# tennka4.net
KiCad netlist of a schematic drawn in EAGLE
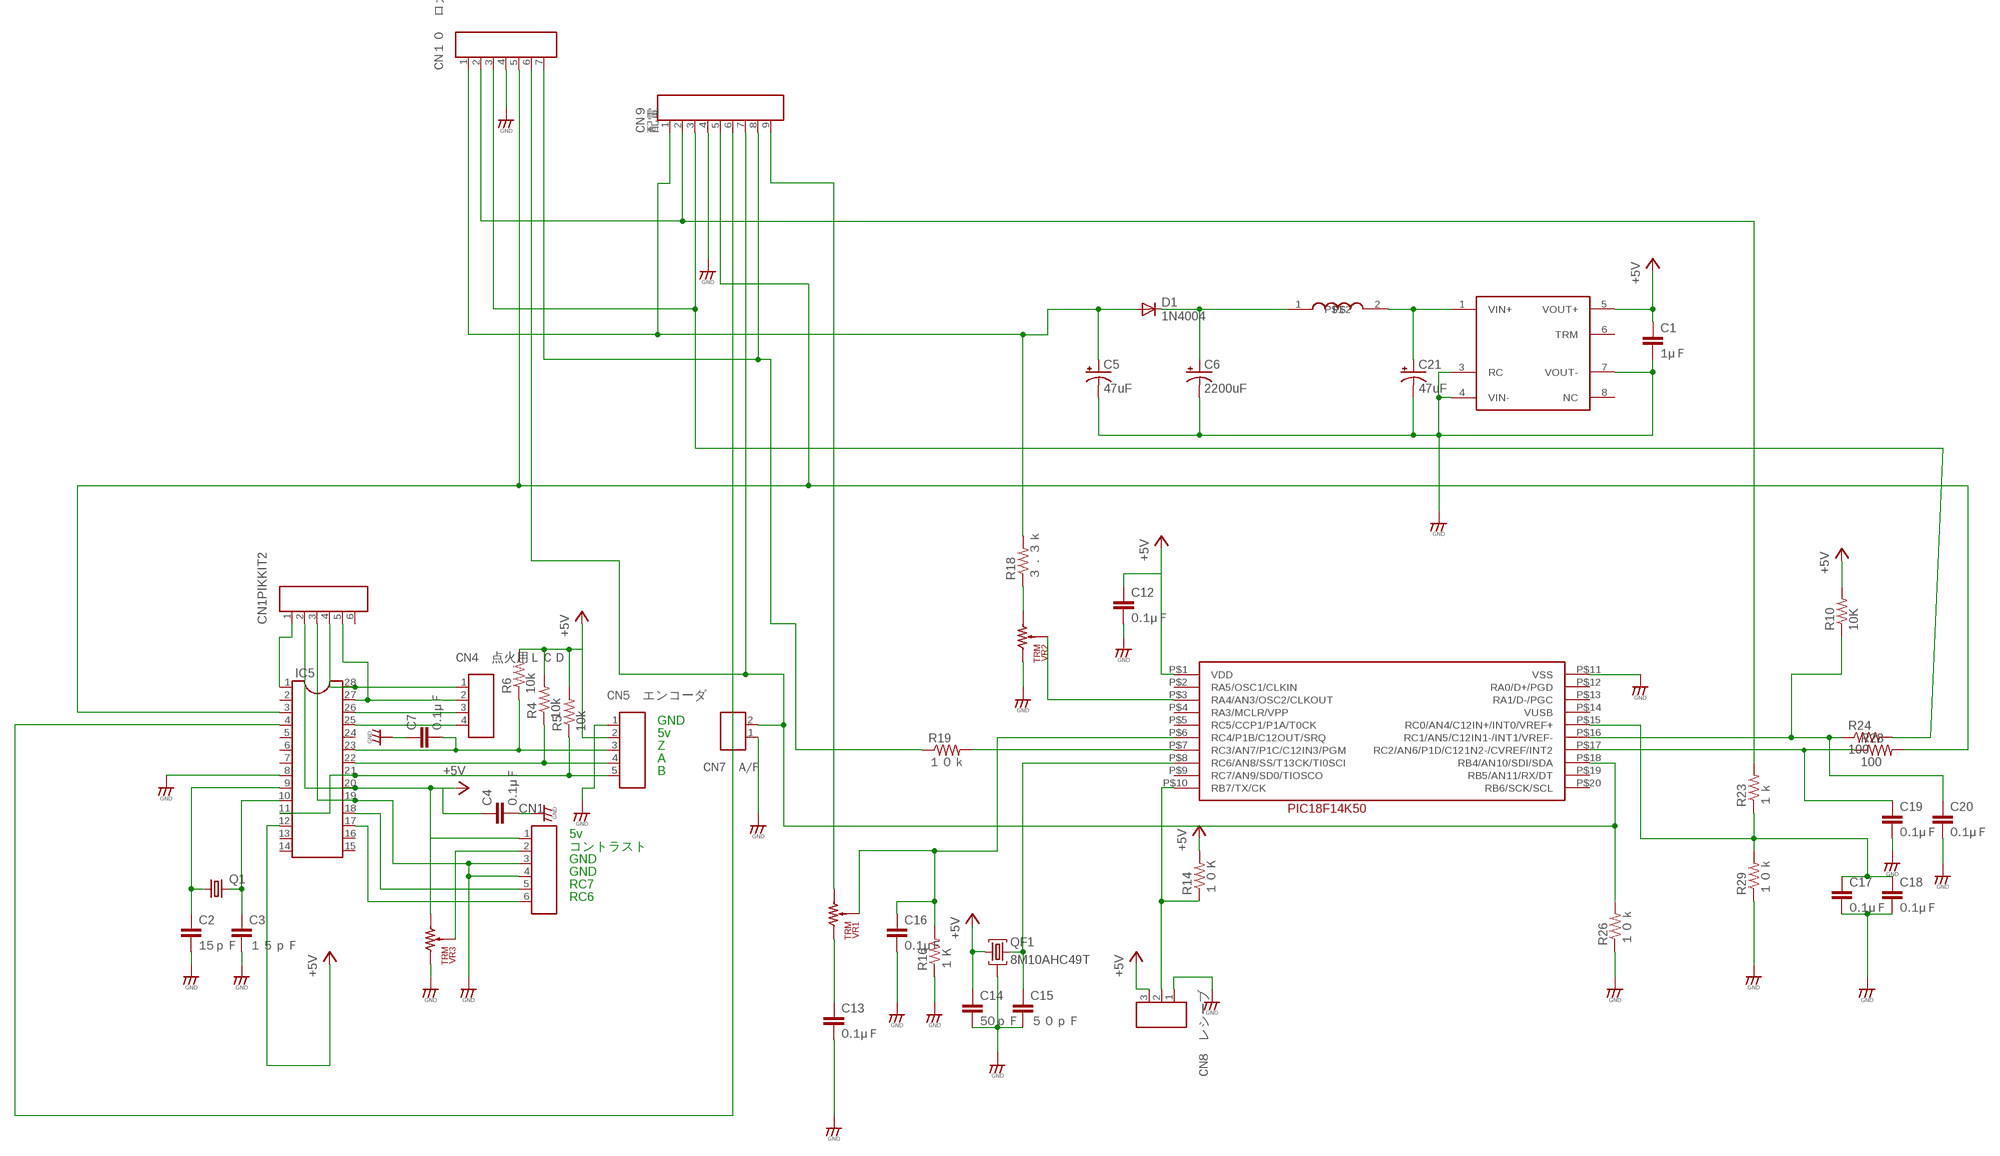
[diagram p0: schematic, sheet 1]

(export (version "E")
  (design (tool "Eeschema 10.0.6"))
  (components
    (comp (ref "C1")
      (value "1μＦ")
      (footprint "eagle-import:C025-024X044")
      (libsource (lib "eagle-import") (part "C-EU025-024X044"))
    )
    (comp (ref "C2")
      (value "15ｐＦ")
      (footprint "eagle-import:C025-024X044")
      (libsource (lib "eagle-import") (part "C-EU025-024X044"))
    )
    (comp (ref "C3")
      (value "１５ｐＦ")
      (footprint "eagle-import:C025-024X044")
      (libsource (lib "eagle-import") (part "C-EU025-024X044"))
    )
    (comp (ref "C4")
      (value "0.1μＦ")
      (footprint "eagle-import:C025-024X044")
      (libsource (lib "eagle-import") (part "C-EU025-024X044"))
    )
    (comp (ref "C5")
      (value "47uF")
      (footprint "eagle-import:E2-4")
      (libsource (lib "eagle-import") (part "CPOL-USE2-4"))
    )
    (comp (ref "C6")
      (value "2200uF")
      (footprint "eagle-import:E5-13")
      (libsource (lib "eagle-import") (part "CPOL-USE5-13"))
    )
    (comp (ref "C7")
      (value "0.1μＦ")
      (footprint "eagle-import:C025-024X044")
      (libsource (lib "eagle-import") (part "C-EU025-024X044"))
    )
    (comp (ref "C12")
      (value "0.1μＦ")
      (footprint "eagle-import:C025-024X044")
      (libsource (lib "eagle-import") (part "C-EU025-024X044"))
    )
    (comp (ref "C13")
      (value "0.1μＦ")
      (footprint "eagle-import:C025-024X044")
      (libsource (lib "eagle-import") (part "C-EU025-024X044"))
    )
    (comp (ref "C14")
      (value "50ｐＦ")
      (footprint "eagle-import:C025-024X044")
      (libsource (lib "eagle-import") (part "C-EU025-024X044"))
    )
    (comp (ref "C15")
      (value "５０ｐＦ")
      (footprint "eagle-import:C025-024X044")
      (libsource (lib "eagle-import") (part "C-EU025-024X044"))
    )
    (comp (ref "C16")
      (value "0.1μＦ")
      (footprint "eagle-import:C025-024X044")
      (libsource (lib "eagle-import") (part "C-EU025-024X044"))
    )
    (comp (ref "C17")
      (value "0.1μＦ")
      (footprint "eagle-import:C025-024X044")
      (libsource (lib "eagle-import") (part "C-EU025-024X044"))
    )
    (comp (ref "C18")
      (value "0.1μＦ")
      (footprint "eagle-import:C025-024X044")
      (libsource (lib "eagle-import") (part "C-EU025-024X044"))
    )
    (comp (ref "C19")
      (value "0.1μＦ")
      (footprint "eagle-import:C025-024X044")
      (libsource (lib "eagle-import") (part "C-EU025-024X044"))
    )
    (comp (ref "C20")
      (value "0.1μＦ")
      (footprint "eagle-import:C025-024X044")
      (libsource (lib "eagle-import") (part "C-EU025-024X044"))
    )
    (comp (ref "C21")
      (value "47uF")
      (footprint "eagle-import:E2-4")
      (libsource (lib "eagle-import") (part "CPOL-USE2-4"))
    )
    (comp (ref "CN1")
      (value "CON_6P")
      (footprint "eagle-import:CON_HRS_DIP_6")
      (libsource (lib "eagle-import") (part "CON_6P"))
    )
    (comp (ref "CN1PIKKIT2")
      (value "CON_6P")
      (footprint "eagle-import:CON_HRS_DIP_6")
      (libsource (lib "eagle-import") (part "CON_6P"))
    )
    (comp (ref "CN4　点火用ＬＣＤ")
      (value "CON_4P")
      (footprint "eagle-import:CON_HRS_DIP_4")
      (libsource (lib "eagle-import") (part "CON_4P"))
    )
    (comp (ref "CN5　エンコーダ")
      (value "CON_5P")
      (footprint "eagle-import:CON_HRS_DIP_5")
      (libsource (lib "eagle-import") (part "CON_5P"))
    )
    (comp (ref "CN7　A/F")
      (value "CON_2P")
      (footprint "eagle-import:CON_HRS_DIP_2")
      (libsource (lib "eagle-import") (part "CON_2P"))
    )
    (comp (ref "CN8　レシーブ")
      (value "CON_3P")
      (footprint "eagle-import:CON_HRS_DIP_3")
      (libsource (lib "eagle-import") (part "CON_3P"))
    )
    (comp (ref "CN１０　ロガー")
      (value "CON_7P")
      (footprint "eagle-import:CON_HRS_DIP_7")
      (libsource (lib "eagle-import") (part "CON_7P"))
    )
    (comp (ref "CN９")
      (value "配電")
      (footprint "eagle-import:CON_HRS_DIP_9")
      (libsource (lib "eagle-import") (part "CON_9P"))
    )
    (comp (ref "D1")
      (value "1N4004")
      (footprint "eagle-import:DO41-10")
      (libsource (lib "eagle-import") (part "1N4004"))
    )
    (comp (ref "IC5")
      (value "DIL28-3")
      (footprint "eagle-import:DIL28-3")
      (libsource (lib "eagle-import") (part "DIL28-3"))
    )
    (comp (ref "IC6")
      (value "PIC18F14K50")
      (footprint "eagle-import:PIC18F14K50")
      (libsource (lib "eagle-import") (part "PIC18F14K50"))
    )
    (comp (ref "LHL13NB101K1")
      (value "LHL13NB101K")
      (footprint "eagle-import:LHL13NB101K")
      (libsource (lib "eagle-import") (part "LHL13NB101K"))
    )
    (comp (ref "Q1")
      (value "CRYSTALHC49S")
      (footprint "eagle-import:HC49_S")
      (libsource (lib "eagle-import") (part "CRYSTALHC49S"))
    )
    (comp (ref "QF1")
      (value "8M10AHC49T")
      (footprint "eagle-import:HC49U")
      (libsource (lib "eagle-import") (part "8M10AHC49T"))
    )
    (comp (ref "R4")
      (value "10k")
      (footprint "eagle-import:0207_7")
      (libsource (lib "eagle-import") (part "R-US_0207/7"))
    )
    (comp (ref "R5")
      (value "10k")
      (footprint "eagle-import:0207_7")
      (libsource (lib "eagle-import") (part "R-US_0207/7"))
    )
    (comp (ref "R6")
      (value "10k")
      (footprint "eagle-import:0207_7")
      (libsource (lib "eagle-import") (part "R-US_0207/7"))
    )
    (comp (ref "R10")
      (value "10K")
      (footprint "eagle-import:0207_7")
      (libsource (lib "eagle-import") (part "R-US_0207/7"))
    )
    (comp (ref "R14")
      (value "１０Ｋ")
      (footprint "eagle-import:0207_7")
      (libsource (lib "eagle-import") (part "R-US_0207/7"))
    )
    (comp (ref "R16")
      (value "１Ｋ")
      (footprint "eagle-import:0207_7")
      (libsource (lib "eagle-import") (part "R-US_0207/7"))
    )
    (comp (ref "R18")
      (value "３．３ｋ")
      (footprint "eagle-import:0207_7")
      (libsource (lib "eagle-import") (part "R-US_0207/7"))
    )
    (comp (ref "R19")
      (value "１０ｋ")
      (footprint "eagle-import:0207_7")
      (libsource (lib "eagle-import") (part "R-US_0207/7"))
    )
    (comp (ref "R23")
      (value "１ｋ")
      (footprint "eagle-import:0207_7")
      (libsource (lib "eagle-import") (part "R-US_0207/7"))
    )
    (comp (ref "R24")
      (value "100")
      (footprint "eagle-import:0207_7")
      (libsource (lib "eagle-import") (part "R-US_0207/7"))
    )
    (comp (ref "R26")
      (value "１０ｋ")
      (footprint "eagle-import:0207_7")
      (libsource (lib "eagle-import") (part "R-US_0207/7"))
    )
    (comp (ref "R28")
      (value "100")
      (footprint "eagle-import:0207_7")
      (libsource (lib "eagle-import") (part "R-US_0207/7"))
    )
    (comp (ref "R29")
      (value "１０ｋ")
      (footprint "eagle-import:0207_7")
      (libsource (lib "eagle-import") (part "R-US_0207/7"))
    )
    (comp (ref "U$3")
      (value "DCDC-CC3-1205SF-E")
      (footprint "eagle-import:DCDC-CC3-1205SF-E")
      (libsource (lib "eagle-import") (part "DCDC-CC3-1205SF-E"))
    )
    (comp (ref "VR1")
      (value "TRM")
      (footprint "eagle-import:TRM")
      (libsource (lib "eagle-import") (part "TRM"))
    )
    (comp (ref "VR2")
      (value "TRM")
      (footprint "eagle-import:TRM")
      (libsource (lib "eagle-import") (part "TRM"))
    )
    (comp (ref "VR3")
      (value "TRM")
      (footprint "eagle-import:TRM")
      (libsource (lib "eagle-import") (part "TRM"))
    )
  )
  (nets
    (net (code "1") (name "+5V") (class "Default")
      (node (ref "C1") (pin "1") (pinfunction "1_1") (pintype "passive"))
      (node (ref "C12") (pin "1") (pinfunction "1_1") (pintype "passive"))
      (node (ref "C14") (pin "1") (pinfunction "1_1") (pintype "passive"))
      (node (ref "C4") (pin "1") (pinfunction "1_1") (pintype "passive"))
      (node (ref "CN1") (pin "1") (pinfunction "1_1") (pintype "passive"))
      (node (ref "CN1PIKKIT2") (pin "2") (pinfunction "2_2") (pintype "passive"))
      (node (ref "CN5　エンコーダ") (pin "2") (pinfunction "2_2") (pintype "passive"))
      (node (ref "CN8　レシーブ") (pin "3") (pinfunction "3_3") (pintype "passive"))
      (node (ref "IC5") (pin "12") (pinfunction "12_12") (pintype "passive"))
      (node (ref "IC5") (pin "20") (pinfunction "20_20") (pintype "passive"))
      (node (ref "IC6") (pin "P$1") (pinfunction "VDD_P$1") (pintype "power_in"))
      (node (ref "QF1") (pin "1") (pinfunction "1_1") (pintype "passive"))
      (node (ref "R10") (pin "2") (pinfunction "2_2") (pintype "passive"))
      (node (ref "R14") (pin "2") (pinfunction "2_2") (pintype "passive"))
      (node (ref "R4") (pin "2") (pinfunction "2_2") (pintype "passive"))
      (node (ref "R5") (pin "2") (pinfunction "2_2") (pintype "passive"))
      (node (ref "R6") (pin "2") (pinfunction "2_2") (pintype "passive"))
      (node (ref "U$3") (pin "5") (pinfunction "VOUT+_5") (pintype "bidirectional"))
      (node (ref "VR3") (pin "P$1") (pinfunction "P$1_P$1") (pintype "passive"))
    )
    (net (code "2") (name "/RA3{slash}MCLR{slash}VPP") (class "Default")
      (node (ref "IC6") (pin "P$4") (pinfunction "RA3/MCLR/VPP_P$4") (pintype "power_in"))
    )
    (net (code "3") (name "GND") (class "Default")
      (node (ref "C1") (pin "2") (pinfunction "2_2") (pintype "passive"))
      (node (ref "C12") (pin "2") (pinfunction "2_2") (pintype "passive"))
      (node (ref "C13") (pin "2") (pinfunction "2_2") (pintype "passive"))
      (node (ref "C14") (pin "2") (pinfunction "2_2") (pintype "passive"))
      (node (ref "C15") (pin "2") (pinfunction "2_2") (pintype "passive"))
      (node (ref "C16") (pin "2") (pinfunction "2_2") (pintype "passive"))
      (node (ref "C17") (pin "2") (pinfunction "2_2") (pintype "passive"))
      (node (ref "C18") (pin "2") (pinfunction "2_2") (pintype "passive"))
      (node (ref "C19") (pin "2") (pinfunction "2_2") (pintype "passive"))
      (node (ref "C2") (pin "2") (pinfunction "2_2") (pintype "passive"))
      (node (ref "C20") (pin "2") (pinfunction "2_2") (pintype "passive"))
      (node (ref "C21") (pin "-") (pinfunction "-_-") (pintype "passive"))
      (node (ref "C3") (pin "2") (pinfunction "2_2") (pintype "passive"))
      (node (ref "C4") (pin "2") (pinfunction "2_2") (pintype "passive"))
      (node (ref "C5") (pin "-") (pinfunction "-_-") (pintype "passive"))
      (node (ref "C6") (pin "-") (pinfunction "-_-") (pintype "passive"))
      (node (ref "C7") (pin "1") (pinfunction "1_1") (pintype "passive"))
      (node (ref "CN1") (pin "3") (pinfunction "3_3") (pintype "passive"))
      (node (ref "CN1") (pin "4") (pinfunction "4_4") (pintype "passive"))
      (node (ref "CN1PIKKIT2") (pin "3") (pinfunction "3_3") (pintype "passive"))
      (node (ref "CN5　エンコーダ") (pin "1") (pinfunction "1_1") (pintype "passive"))
      (node (ref "CN7　A/F") (pin "1") (pinfunction "1_1") (pintype "passive"))
      (node (ref "CN8　レシーブ") (pin "1") (pinfunction "1_1") (pintype "passive"))
      (node (ref "CN１０　ロガー") (pin "4") (pinfunction "4_4") (pintype "passive"))
      (node (ref "CN９") (pin "4") (pinfunction "4_4") (pintype "passive"))
      (node (ref "IC5") (pin "19") (pinfunction "19_19") (pintype "passive"))
      (node (ref "IC5") (pin "8") (pinfunction "8_8") (pintype "passive"))
      (node (ref "IC6") (pin "P$11") (pinfunction "VSS_P$11") (pintype "power_in"))
      (node (ref "QF1") (pin "2") (pinfunction "2_2") (pintype "passive"))
      (node (ref "R16") (pin "1") (pinfunction "1_1") (pintype "passive"))
      (node (ref "R26") (pin "1") (pinfunction "1_1") (pintype "passive"))
      (node (ref "R29") (pin "1") (pinfunction "1_1") (pintype "passive"))
      (node (ref "U$3") (pin "3") (pinfunction "RC_3") (pintype "bidirectional"))
      (node (ref "U$3") (pin "4") (pinfunction "VIN-_4") (pintype "bidirectional"))
      (node (ref "U$3") (pin "7") (pinfunction "VOUT-_7") (pintype "bidirectional"))
      (node (ref "VR2") (pin "P$3") (pinfunction "P$3_P$3") (pintype "passive"))
      (node (ref "VR3") (pin "P$3") (pinfunction "P$3_P$3") (pintype "passive"))
    )
    (net (code "4") (name "Net-(C2-Pad1)") (class "Default")
      (node (ref "C2") (pin "1") (pinfunction "1_1") (pintype "passive"))
      (node (ref "IC5") (pin "9") (pinfunction "9_9") (pintype "passive"))
      (node (ref "Q1") (pin "1") (pinfunction "1_1") (pintype "passive"))
    )
    (net (code "5") (name "Net-(C3-Pad1)") (class "Default")
      (node (ref "C3") (pin "1") (pinfunction "1_1") (pintype "passive"))
      (node (ref "IC5") (pin "10") (pinfunction "10_10") (pintype "passive"))
      (node (ref "Q1") (pin "2") (pinfunction "2_2") (pintype "passive"))
    )
    (net (code "6") (name "Net-(C5-Pad+)") (class "Default")
      (node (ref "C5") (pin "+") (pinfunction "+_+") (pintype "passive"))
      (node (ref "CN１０　ロガー") (pin "1") (pinfunction "1_1") (pintype "passive"))
      (node (ref "CN９") (pin "1") (pinfunction "1_1") (pintype "passive"))
      (node (ref "D1") (pin "A") (pinfunction "A_A") (pintype "passive"))
      (node (ref "R18") (pin "2") (pinfunction "2_2") (pintype "passive"))
    )
    (net (code "7") (name "Net-(C7-Pad2)") (class "Default")
      (node (ref "C7") (pin "2") (pinfunction "2_2") (pintype "passive"))
      (node (ref "CN5　エンコーダ") (pin "3") (pinfunction "3_3") (pintype "passive"))
      (node (ref "IC5") (pin "23") (pinfunction "23_23") (pintype "passive"))
      (node (ref "R6") (pin "1") (pinfunction "1_1") (pintype "passive"))
    )
    (net (code "8") (name "Net-(C13-Pad1)") (class "Default")
      (node (ref "C13") (pin "1") (pinfunction "1_1") (pintype "passive"))
      (node (ref "VR1") (pin "P$3") (pinfunction "P$3_P$3") (pintype "passive"))
    )
    (net (code "9") (name "Net-(CN1-Pad2)") (class "Default")
      (node (ref "CN1") (pin "2") (pinfunction "2_2") (pintype "passive"))
      (node (ref "VR3") (pin "P$2") (pinfunction "P$2_P$2") (pintype "passive"))
    )
    (net (code "10") (name "Net-(CN1-Pad5)") (class "Default")
      (node (ref "CN1") (pin "5") (pinfunction "5_5") (pintype "passive"))
      (node (ref "IC5") (pin "18") (pinfunction "18_18") (pintype "passive"))
    )
    (net (code "11") (name "Net-(CN1-Pad6)") (class "Default")
      (node (ref "CN1") (pin "6") (pinfunction "6_6") (pintype "passive"))
      (node (ref "IC5") (pin "17") (pinfunction "17_17") (pintype "passive"))
    )
    (net (code "12") (name "Net-(CN1PIKKIT2-Pad1)") (class "Default")
      (node (ref "CN1PIKKIT2") (pin "1") (pinfunction "1_1") (pintype "passive"))
      (node (ref "IC5") (pin "1") (pinfunction "1_1") (pintype "passive"))
    )
    (net (code "13") (name "Net-(CN1PIKKIT2-Pad4)") (class "Default")
      (node (ref "CN1PIKKIT2") (pin "4") (pinfunction "4_4") (pintype "passive"))
      (node (ref "CN4　点火用ＬＣＤ") (pin "1") (pinfunction "1_1") (pintype "passive"))
      (node (ref "IC5") (pin "28") (pinfunction "28_28") (pintype "passive"))
    )
    (net (code "14") (name "Net-(CN1PIKKIT2-Pad5)") (class "Default")
      (node (ref "CN1PIKKIT2") (pin "5") (pinfunction "5_5") (pintype "passive"))
      (node (ref "CN4　点火用ＬＣＤ") (pin "2") (pinfunction "2_2") (pintype "passive"))
      (node (ref "IC5") (pin "27") (pinfunction "27_27") (pintype "passive"))
    )
    (net (code "15") (name "Net-(CN4　点火用ＬＣＤ-Pad3)") (class "Default")
      (node (ref "CN4　点火用ＬＣＤ") (pin "3") (pinfunction "3_3") (pintype "passive"))
      (node (ref "IC5") (pin "26") (pinfunction "26_26") (pintype "passive"))
    )
    (net (code "16") (name "Net-(CN4　点火用ＬＣＤ-Pad4)") (class "Default")
      (node (ref "CN4　点火用ＬＣＤ") (pin "4") (pinfunction "4_4") (pintype "passive"))
      (node (ref "IC5") (pin "25") (pinfunction "25_25") (pintype "passive"))
    )
    (net (code "17") (name "Net-(CN5　エンコーダ-Pad4)") (class "Default")
      (node (ref "CN5　エンコーダ") (pin "4") (pinfunction "4_4") (pintype "passive"))
      (node (ref "IC5") (pin "22") (pinfunction "22_22") (pintype "passive"))
      (node (ref "R4") (pin "1") (pinfunction "1_1") (pintype "passive"))
    )
    (net (code "18") (name "Net-(CN5　エンコーダ-Pad5)") (class "Default")
      (node (ref "CN5　エンコーダ") (pin "5") (pinfunction "5_5") (pintype "passive"))
      (node (ref "IC5") (pin "11") (pinfunction "11_11") (pintype "passive"))
      (node (ref "IC5") (pin "21") (pinfunction "21_21") (pintype "passive"))
      (node (ref "R5") (pin "1") (pinfunction "1_1") (pintype "passive"))
    )
    (net (code "19") (name "Net-(CN１０　ロガー-Pad2)") (class "Default")
      (node (ref "CN１０　ロガー") (pin "2") (pinfunction "2_2") (pintype "passive"))
      (node (ref "CN９") (pin "2") (pinfunction "2_2") (pintype "passive"))
      (node (ref "R23") (pin "2") (pinfunction "2_2") (pintype "passive"))
    )
    (net (code "20") (name "Net-(CN１０　ロガー-Pad3)") (class "Default")
      (node (ref "CN１０　ロガー") (pin "3") (pinfunction "3_3") (pintype "passive"))
      (node (ref "CN９") (pin "3") (pinfunction "3_3") (pintype "passive"))
      (node (ref "R24") (pin "2") (pinfunction "2_2") (pintype "passive"))
    )
    (net (code "21") (name "Net-(CN１０　ロガー-Pad5)") (class "Default")
      (node (ref "CN１０　ロガー") (pin "5") (pinfunction "5_5") (pintype "passive"))
      (node (ref "CN９") (pin "5") (pinfunction "5_5") (pintype "passive"))
      (node (ref "IC5") (pin "3") (pinfunction "3_3") (pintype "passive"))
      (node (ref "R28") (pin "2") (pinfunction "2_2") (pintype "passive"))
    )
    (net (code "22") (name "Net-(CN１０　ロガー-Pad7)") (class "Default")
      (node (ref "CN１０　ロガー") (pin "7") (pinfunction "7_7") (pintype "passive"))
      (node (ref "CN９") (pin "8") (pinfunction "8_8") (pintype "passive"))
      (node (ref "R19") (pin "1") (pinfunction "1_1") (pintype "passive"))
    )
    (net (code "23") (name "Net-(CN９-Pad6)") (class "Default")
      (node (ref "CN９") (pin "6") (pinfunction "6_6") (pintype "passive"))
      (node (ref "IC5") (pin "4") (pinfunction "4_4") (pintype "passive"))
    )
    (net (code "24") (name "Net-(CN９-Pad9)") (class "Default")
      (node (ref "CN９") (pin "9") (pinfunction "9_9") (pintype "passive"))
      (node (ref "VR1") (pin "P$1") (pinfunction "P$1_P$1") (pintype "passive"))
    )
    (net (code "25") (name "Net-(IC6-RA4{slash}AN3{slash}OSC2{slash}CLKOUT)") (class "Default")
      (node (ref "IC6") (pin "P$3") (pinfunction "RA4/AN3/OSC2/CLKOUT_P$3") (pintype "bidirectional"))
      (node (ref "VR2") (pin "P$2") (pinfunction "P$2_P$2") (pintype "passive"))
    )
    (net (code "26") (name "Net-(IC6-RB4{slash}AN10{slash}SDI{slash}SDA)") (class "Default")
      (node (ref "CN7　A/F") (pin "2") (pinfunction "2_2") (pintype "passive"))
      (node (ref "CN１０　ロガー") (pin "6") (pinfunction "6_6") (pintype "passive"))
      (node (ref "CN９") (pin "7") (pinfunction "7_7") (pintype "passive"))
      (node (ref "IC6") (pin "P$18") (pinfunction "RB4/AN10/SDI/SDA_P$18") (pintype "bidirectional"))
      (node (ref "R26") (pin "2") (pinfunction "2_2") (pintype "passive"))
    )
    (net (code "27") (name "Net-(IC6-RB7{slash}TX{slash}CK)") (class "Default")
      (node (ref "CN8　レシーブ") (pin "2") (pinfunction "2_2") (pintype "passive"))
      (node (ref "IC6") (pin "P$10") (pinfunction "RB7/TX/CK_P$10") (pintype "bidirectional"))
      (node (ref "R14") (pin "1") (pinfunction "1_1") (pintype "passive"))
    )
    (net (code "28") (name "Net-(IC6-RC0{slash}AN4{slash}C12IN+{slash}INT0{slash}VREF+)") (class "Default")
      (node (ref "C17") (pin "1") (pinfunction "1_1") (pintype "passive"))
      (node (ref "C18") (pin "1") (pinfunction "1_1") (pintype "passive"))
      (node (ref "IC6") (pin "P$15") (pinfunction "RC0/AN4/C12IN+/INT0/VREF+_P$15") (pintype "input"))
      (node (ref "R23") (pin "1") (pinfunction "1_1") (pintype "passive"))
      (node (ref "R29") (pin "2") (pinfunction "2_2") (pintype "passive"))
    )
    (net (code "29") (name "Net-(IC6-RC1{slash}AN5{slash}C12IN1-{slash}INT1{slash}VREF-)") (class "Default")
      (node (ref "C20") (pin "1") (pinfunction "1_1") (pintype "passive"))
      (node (ref "IC6") (pin "P$16") (pinfunction "RC1/AN5/C12IN1-/INT1/VREF-_P$16") (pintype "bidirectional"))
      (node (ref "R10") (pin "1") (pinfunction "1_1") (pintype "passive"))
      (node (ref "R24") (pin "1") (pinfunction "1_1") (pintype "passive"))
    )
    (net (code "30") (name "Net-(IC6-RC2{slash}AN6{slash}P1D{slash}C121N2-{slash}CVREF{slash}INT2)") (class "Default")
      (node (ref "C19") (pin "1") (pinfunction "1_1") (pintype "passive"))
      (node (ref "IC6") (pin "P$17") (pinfunction "RC2/AN6/P1D/C121N2-/CVREF/INT2_P$17") (pintype "bidirectional"))
      (node (ref "R28") (pin "1") (pinfunction "1_1") (pintype "passive"))
    )
    (net (code "31") (name "Net-(IC6-RC3{slash}AN7{slash}P1C{slash}C12IN3{slash}PGM)") (class "Default")
      (node (ref "IC6") (pin "P$7") (pinfunction "RC3/AN7/P1C/C12IN3/PGM_P$7") (pintype "bidirectional"))
      (node (ref "R19") (pin "2") (pinfunction "2_2") (pintype "passive"))
    )
    (net (code "32") (name "Net-(IC6-RC4{slash}P1B{slash}C12OUT{slash}SRQ)") (class "Default")
      (node (ref "C16") (pin "1") (pinfunction "1_1") (pintype "passive"))
      (node (ref "IC6") (pin "P$6") (pinfunction "RC4/P1B/C12OUT/SRQ_P$6") (pintype "bidirectional"))
      (node (ref "R16") (pin "2") (pinfunction "2_2") (pintype "passive"))
      (node (ref "VR1") (pin "P$2") (pinfunction "P$2_P$2") (pintype "passive"))
    )
    (net (code "33") (name "Net-(IC6-RC6{slash}AN8{slash}SS{slash}T13CK{slash}TI0SCI)") (class "Default")
      (node (ref "C15") (pin "1") (pinfunction "1_1") (pintype "passive"))
      (node (ref "IC6") (pin "P$8") (pinfunction "RC6/AN8/SS/T13CK/TI0SCI_P$8") (pintype "bidirectional"))
      (node (ref "QF1") (pin "3") (pinfunction "3_3") (pintype "passive"))
    )
    (net (code "34") (name "Net-(LHL13NB101K1-P$1)") (class "Default")
      (node (ref "C6") (pin "+") (pinfunction "+_+") (pintype "passive"))
      (node (ref "D1") (pin "C") (pinfunction "C_C") (pintype "passive"))
      (node (ref "LHL13NB101K1") (pin "1") (pinfunction "P$1_1") (pintype "bidirectional"))
    )
    (net (code "35") (name "Net-(LHL13NB101K1-P$2)") (class "Default")
      (node (ref "C21") (pin "+") (pinfunction "+_+") (pintype "passive"))
      (node (ref "LHL13NB101K1") (pin "2") (pinfunction "P$2_2") (pintype "bidirectional"))
      (node (ref "U$3") (pin "1") (pinfunction "VIN+_1") (pintype "bidirectional"))
    )
    (net (code "36") (name "Net-(R18-Pad1)") (class "Default")
      (node (ref "R18") (pin "1") (pinfunction "1_1") (pintype "passive"))
      (node (ref "VR2") (pin "P$1") (pinfunction "P$1_P$1") (pintype "passive"))
    )
    (net (code "37") (name "unconnected-(CN1PIKKIT2-Pad6)") (class "Default")
      (node (ref "CN1PIKKIT2") (pin "6") (pinfunction "6_6") (pintype "passive"))
    )
    (net (code "38") (name "unconnected-(IC5-Pad2)") (class "Default")
      (node (ref "IC5") (pin "2") (pinfunction "2_2") (pintype "passive"))
    )
    (net (code "39") (name "unconnected-(IC5-Pad5)") (class "Default")
      (node (ref "IC5") (pin "5") (pinfunction "5_5") (pintype "passive"))
    )
    (net (code "40") (name "unconnected-(IC5-Pad6)") (class "Default")
      (node (ref "IC5") (pin "6") (pinfunction "6_6") (pintype "passive"))
    )
    (net (code "41") (name "unconnected-(IC5-Pad7)") (class "Default")
      (node (ref "IC5") (pin "7") (pinfunction "7_7") (pintype "passive"))
    )
    (net (code "42") (name "unconnected-(IC5-Pad13)") (class "Default")
      (node (ref "IC5") (pin "13") (pinfunction "13_13") (pintype "passive"))
    )
    (net (code "43") (name "unconnected-(IC5-Pad14)") (class "Default")
      (node (ref "IC5") (pin "14") (pinfunction "14_14") (pintype "passive"))
    )
    (net (code "44") (name "unconnected-(IC5-Pad15)") (class "Default")
      (node (ref "IC5") (pin "15") (pinfunction "15_15") (pintype "passive"))
    )
    (net (code "45") (name "unconnected-(IC5-Pad16)") (class "Default")
      (node (ref "IC5") (pin "16") (pinfunction "16_16") (pintype "passive"))
    )
    (net (code "46") (name "unconnected-(IC5-Pad24)") (class "Default")
      (node (ref "IC5") (pin "24") (pinfunction "24_24") (pintype "passive"))
    )
    (net (code "47") (name "unconnected-(IC6-RA0{slash}D+{slash}PGD-PadP$12)") (class "Default")
      (node (ref "IC6") (pin "P$12") (pinfunction "RA0/D+/PGD_P$12") (pintype "bidirectional"))
    )
    (net (code "48") (name "unconnected-(IC6-RA1{slash}D-{slash}PGC-PadP$13)") (class "Default")
      (node (ref "IC6") (pin "P$13") (pinfunction "RA1/D-/PGC_P$13") (pintype "bidirectional"))
    )
    (net (code "49") (name "unconnected-(IC6-RA5{slash}OSC1{slash}CLKIN-PadP$2)") (class "Default")
      (node (ref "IC6") (pin "P$2") (pinfunction "RA5/OSC1/CLKIN_P$2") (pintype "bidirectional"))
    )
    (net (code "50") (name "unconnected-(IC6-RB5{slash}AN11{slash}RX{slash}DT-PadP$19)") (class "Default")
      (node (ref "IC6") (pin "P$19") (pinfunction "RB5/AN11/RX/DT_P$19") (pintype "bidirectional"))
    )
    (net (code "51") (name "unconnected-(IC6-RB6{slash}SCK{slash}SCL-PadP$20)") (class "Default")
      (node (ref "IC6") (pin "P$20") (pinfunction "RB6/SCK/SCL_P$20") (pintype "bidirectional"))
    )
    (net (code "52") (name "unconnected-(IC6-RC5{slash}CCP1{slash}P1A{slash}T0CK-PadP$5)") (class "Default")
      (node (ref "IC6") (pin "P$5") (pinfunction "RC5/CCP1/P1A/T0CK_P$5") (pintype "bidirectional"))
    )
    (net (code "53") (name "unconnected-(IC6-RC7{slash}AN9{slash}SD0{slash}TIOSCO-PadP$9)") (class "Default")
      (node (ref "IC6") (pin "P$9") (pinfunction "RC7/AN9/SD0/TIOSCO_P$9") (pintype "bidirectional"))
    )
    (net (code "54") (name "unconnected-(IC6-VUSB-PadP$14)") (class "Default")
      (node (ref "IC6") (pin "P$14") (pinfunction "VUSB_P$14") (pintype "bidirectional"))
    )
    (net (code "55") (name "unconnected-(U$3-NC-Pad8)") (class "Default")
      (node (ref "U$3") (pin "8") (pinfunction "NC_8") (pintype "bidirectional"))
    )
    (net (code "56") (name "unconnected-(U$3-TRM-Pad6)") (class "Default")
      (node (ref "U$3") (pin "6") (pinfunction "TRM_6") (pintype "bidirectional"))
    )
  )
)
